# VESC_POWER_SCH.net
KiCad netlist of a schematic drawn in Altium Designer
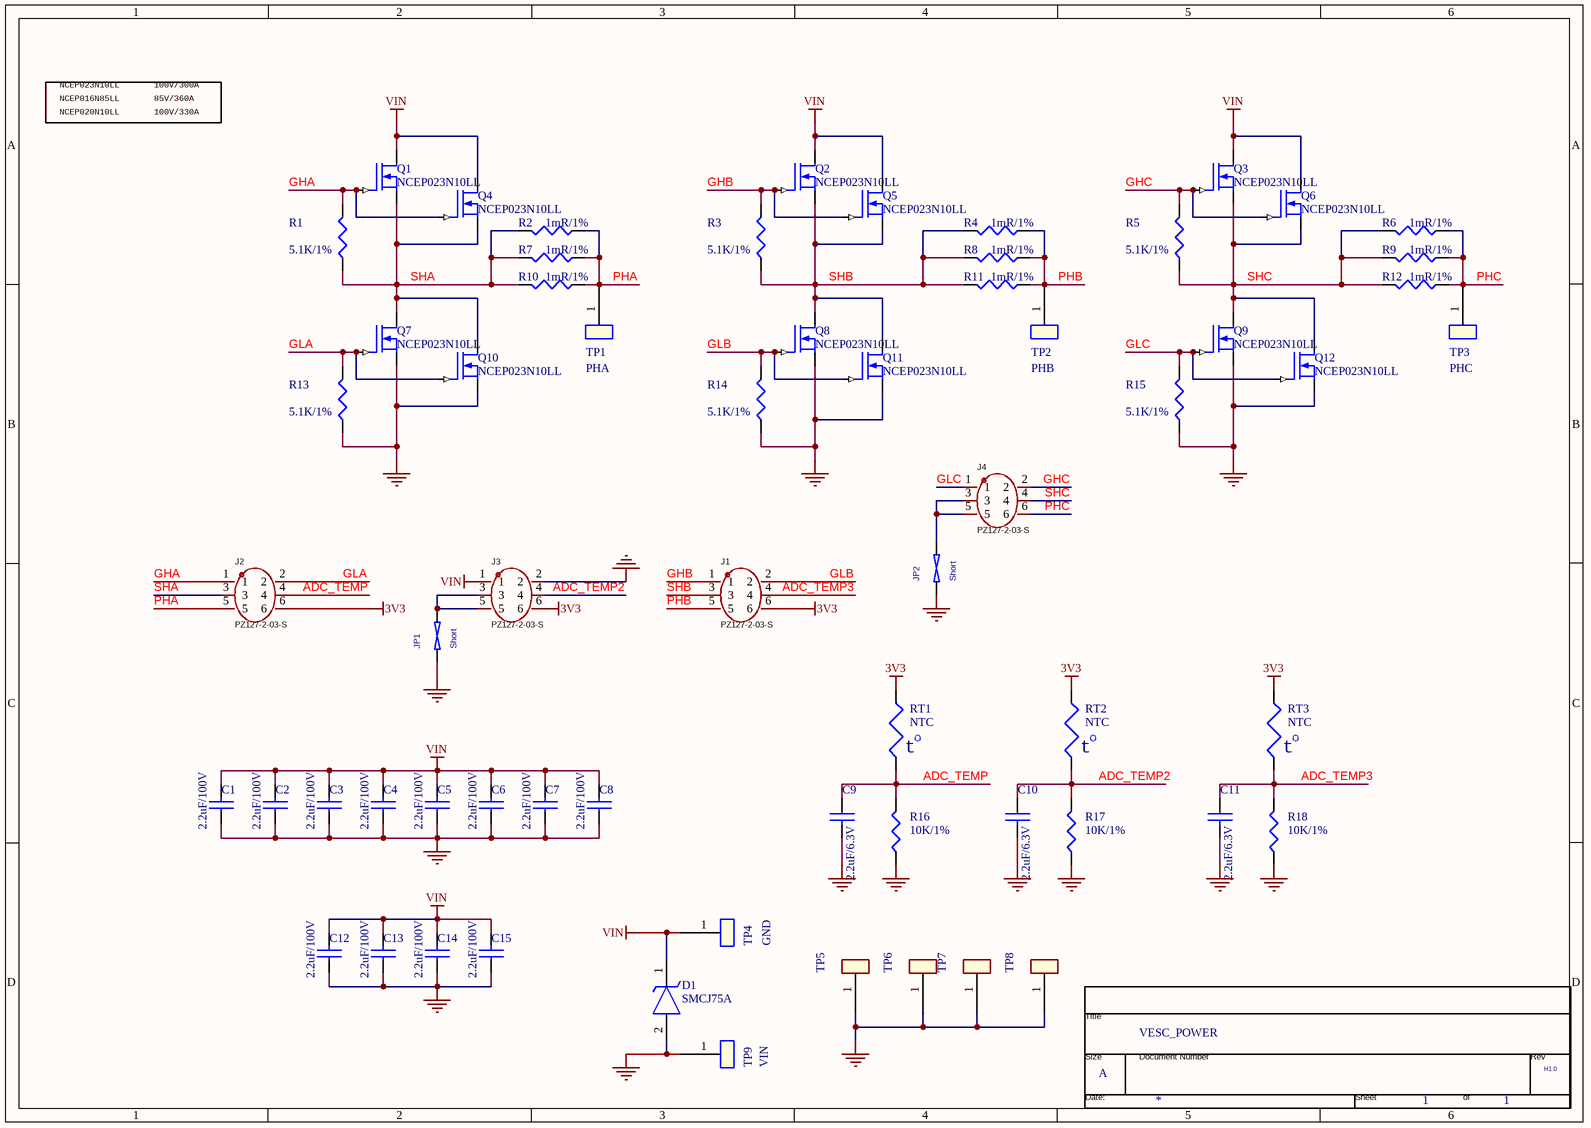
[diagram p0: VESC_POWER_SCH.SchDoc]

(export (version "E")
  (design (tool "Eeschema 10.0.6"))
  (components
    (comp (ref "*")
      (value "TitleBlock0")
      (fields
        (field (name "REVCODE") "H1.0")
        (field (name "TITLE") "VESC_POWER")
        (field (name "PAGE SIZE") "A")
        (field (name "PAGE NUMBER") "1")
        (field (name "PAGE COUNT") "1")
      )
      (libsource (lib "*") (part "TitleBlock0"))
    )
    (comp (ref "C1") (value "2.2uF/100V") (footprint "CAPC3225X230N") (libsource (lib "*") (part "CAP NP")))
    (comp (ref "C2") (value "2.2uF/100V") (footprint "CAPC3225X230N") (libsource (lib "*") (part "CAP NP")))
    (comp (ref "C3") (value "2.2uF/100V") (footprint "CAPC3225X230N") (libsource (lib "*") (part "CAP NP")))
    (comp (ref "C4") (value "2.2uF/100V") (footprint "CAPC3225X230N") (libsource (lib "*") (part "CAP NP")))
    (comp (ref "C5") (value "2.2uF/100V") (footprint "CAPC3225X230N") (libsource (lib "*") (part "CAP NP")))
    (comp (ref "C6") (value "2.2uF/100V") (footprint "CAPC3225X230N") (libsource (lib "*") (part "CAP NP")))
    (comp (ref "C7") (value "2.2uF/100V") (footprint "CAPC3225X230N") (libsource (lib "*") (part "CAP NP")))
    (comp (ref "C8") (value "2.2uF/100V") (footprint "CAPC3225X230N") (libsource (lib "*") (part "CAP NP")))
    (comp (ref "C9") (value "2.2uF/6.3V") (footprint "C0603") (libsource (lib "*") (part "CAP NP")))
    (comp (ref "C10") (value "2.2uF/6.3V") (footprint "C0603") (libsource (lib "*") (part "CAP NP")))
    (comp (ref "C11") (value "2.2uF/6.3V") (footprint "C0603") (libsource (lib "*") (part "CAP NP")))
    (comp (ref "C12") (value "2.2uF/100V") (footprint "CAPC3225X230N") (libsource (lib "*") (part "CAP NP")))
    (comp (ref "C13") (value "2.2uF/100V") (footprint "CAPC3225X230N") (libsource (lib "*") (part "CAP NP")))
    (comp (ref "C14") (value "2.2uF/100V") (footprint "CAPC3225X230N") (libsource (lib "*") (part "CAP NP")))
    (comp (ref "C15") (value "2.2uF/100V") (footprint "CAPC3225X230N") (libsource (lib "*") (part "CAP NP")))
    (comp (ref "D1")
      (value "SMCJ75A")
      (footprint "DIOM7959X262N")
      (description "TVS Diode (Uni-directional)")
      (fields (field (name "MOUSER PART NUMBER") "652-SMCJ75A"))
      (libsource (lib "VESC_POWER_Library") (part "SMCJ75A"))
    )
    (comp (ref "J1")
      (value "PZ127-2-03-S")
      (footprint "HDR-SMD_6P-P1.27-V-M-R2-C3-LS5.3")
      (fields (field (name "MANUFACTURER") "HCTL(华灿天禄)"))
      (libsource (lib "VESC_POWER_Library") (part "PZ127-2-03-S"))
    )
    (comp (ref "J2")
      (value "PZ127-2-03-S")
      (footprint "HDR-SMD_6P-P1.27-V-M-R2-C3-LS5.3")
      (fields (field (name "MANUFACTURER") "HCTL(华灿天禄)"))
      (libsource (lib "VESC_POWER_Library") (part "PZ127-2-03-S"))
    )
    (comp (ref "J3")
      (value "PZ127-2-03-S")
      (footprint "HDR-SMD_6P-P1.27-V-M-R2-C3-LS5.3")
      (fields (field (name "MANUFACTURER") "HCTL(华灿天禄)"))
      (libsource (lib "VESC_POWER_Library") (part "PZ127-2-03-S"))
    )
    (comp (ref "J4")
      (value "PZ127-2-03-S")
      (footprint "HDR-SMD_6P-P1.27-V-M-R2-C3-LS5.3")
      (fields (field (name "MANUFACTURER") "HCTL(华灿天禄)"))
      (libsource (lib "VESC_POWER_Library") (part "PZ127-2-03-S"))
    )
    (comp (ref "JP1")
      (value "Short")
      (footprint "SHORT")
      (description "2 PIN SHORTED TO CONNECT DIFFERENT NETS")
      (fields (field (name "PART_NUMBER") "TMP-442"))
      (libsource (lib "VESC_POWER_Library") (part "SHORT"))
    )
    (comp (ref "JP2")
      (value "Short")
      (footprint "SHORT")
      (description "2 PIN SHORTED TO CONNECT DIFFERENT NETS")
      (fields (field (name "PART_NUMBER") "TMP-442"))
      (libsource (lib "VESC_POWER_Library") (part "SHORT"))
    )
    (comp (ref "Q1") (value "NCEP023N10LL") (footprint "TOLL") (libsource (lib "*") (part "MOSFET N")))
    (comp (ref "Q2") (value "NCEP023N10LL") (footprint "TOLL") (libsource (lib "*") (part "MOSFET N")))
    (comp (ref "Q3") (value "NCEP023N10LL") (footprint "TOLL") (libsource (lib "*") (part "MOSFET N")))
    (comp (ref "Q4") (value "NCEP023N10LL") (footprint "TOLL") (libsource (lib "*") (part "MOSFET N")))
    (comp (ref "Q5") (value "NCEP023N10LL") (footprint "TOLL") (libsource (lib "*") (part "MOSFET N")))
    (comp (ref "Q6") (value "NCEP023N10LL") (footprint "TOLL") (libsource (lib "*") (part "MOSFET N")))
    (comp (ref "Q7") (value "NCEP023N10LL") (footprint "TOLL") (libsource (lib "*") (part "MOSFET N")))
    (comp (ref "Q8") (value "NCEP023N10LL") (footprint "TOLL") (libsource (lib "*") (part "MOSFET N")))
    (comp (ref "Q9") (value "NCEP023N10LL") (footprint "TOLL") (libsource (lib "*") (part "MOSFET N")))
    (comp (ref "Q10") (value "NCEP023N10LL") (footprint "TOLL") (libsource (lib "*") (part "MOSFET N")))
    (comp (ref "Q11") (value "NCEP023N10LL") (footprint "TOLL") (libsource (lib "*") (part "MOSFET N")))
    (comp (ref "Q12") (value "NCEP023N10LL") (footprint "TOLL") (libsource (lib "*") (part "MOSFET N")))
    (comp (ref "R1") (value "5.1K/1%") (footprint "R0603") (libsource (lib "*") (part "RESISTOR")))
    (comp (ref "R2") (value "1mR/1%") (footprint "R2512") (libsource (lib "*") (part "RESISTOR")))
    (comp (ref "R3") (value "5.1K/1%") (footprint "R0603") (libsource (lib "*") (part "RESISTOR")))
    (comp (ref "R4") (value "1mR/1%") (footprint "R2512") (libsource (lib "*") (part "RESISTOR")))
    (comp (ref "R5") (value "5.1K/1%") (footprint "R0603") (libsource (lib "*") (part "RESISTOR")))
    (comp (ref "R6") (value "1mR/1%") (footprint "R2512") (libsource (lib "*") (part "RESISTOR")))
    (comp (ref "R7") (value "1mR/1%") (footprint "R2512") (libsource (lib "*") (part "RESISTOR")))
    (comp (ref "R8") (value "1mR/1%") (footprint "R2512") (libsource (lib "*") (part "RESISTOR")))
    (comp (ref "R9") (value "1mR/1%") (footprint "R2512") (libsource (lib "*") (part "RESISTOR")))
    (comp (ref "R10") (value "1mR/1%") (footprint "R2512") (libsource (lib "*") (part "RESISTOR")))
    (comp (ref "R11") (value "1mR/1%") (footprint "R2512") (libsource (lib "*") (part "RESISTOR")))
    (comp (ref "R12") (value "1mR/1%") (footprint "R2512") (libsource (lib "*") (part "RESISTOR")))
    (comp (ref "R13") (value "5.1K/1%") (footprint "R0603") (libsource (lib "*") (part "RESISTOR")))
    (comp (ref "R14") (value "5.1K/1%") (footprint "R0603") (libsource (lib "*") (part "RESISTOR")))
    (comp (ref "R15") (value "5.1K/1%") (footprint "R0603") (libsource (lib "*") (part "RESISTOR")))
    (comp (ref "R16") (value "10K/1%") (footprint "R0603") (libsource (lib "*") (part "RESISTOR")))
    (comp (ref "R17") (value "10K/1%") (footprint "R0603") (libsource (lib "*") (part "RESISTOR")))
    (comp (ref "R18") (value "10K/1%") (footprint "R0603") (libsource (lib "*") (part "RESISTOR")))
    (comp (ref "RT1") (value "NTC") (footprint "R0603") (libsource (lib "*") (part "NTC")))
    (comp (ref "RT2") (value "NTC") (footprint "R0603") (libsource (lib "*") (part "NTC")))
    (comp (ref "RT3") (value "NTC") (footprint "R0603") (libsource (lib "*") (part "NTC")))
    (comp (ref "TP1") (value "PHA") (footprint "TP_8x8") (libsource (lib "") (part "TEST POINT_1")))
    (comp (ref "TP2") (value "PHB") (footprint "TP_8x8") (libsource (lib "") (part "TEST POINT_1")))
    (comp (ref "TP3") (value "PHC") (footprint "TP_8x8") (libsource (lib "") (part "TEST POINT_1")))
    (comp (ref "TP4") (value "GND") (footprint "TP_8x8") (libsource (lib "*") (part "TEST POINT")))
    (comp (ref "TP5")
      (value "TEST POINT")
      (footprint "HOLE-3.2MM_M")
      (libsource (lib "VESC_POWER_Library") (part "TEST POINT"))
    )
    (comp (ref "TP6")
      (value "TEST POINT")
      (footprint "HOLE-3.2MM_M")
      (libsource (lib "VESC_POWER_Library") (part "TEST POINT"))
    )
    (comp (ref "TP7")
      (value "TEST POINT")
      (footprint "HOLE-3.2MM_M")
      (libsource (lib "VESC_POWER_Library") (part "TEST POINT"))
    )
    (comp (ref "TP8")
      (value "TEST POINT")
      (footprint "HOLE-3.2MM_M")
      (libsource (lib "VESC_POWER_Library") (part "TEST POINT"))
    )
    (comp (ref "TP9") (value "VIN") (footprint "TP_8x8") (libsource (lib "*") (part "TEST POINT")))
  )
  (nets
    (net (code "1") (name "/ADC_TEMP") (class "Default")
      (node (ref "C9") (pin "1") (pinfunction "1_1") (pintype "passive"))
      (node (ref "J2") (pin "4") (pinfunction "4_4") (pintype "passive"))
      (node (ref "R16") (pin "2") (pinfunction "2_2") (pintype "passive"))
      (node (ref "RT1") (pin "2") (pinfunction "2_2") (pintype "passive"))
    )
    (net (code "2") (name "/ADC_TEMP2") (class "Default")
      (node (ref "C10") (pin "1") (pinfunction "1_1") (pintype "passive"))
      (node (ref "J3") (pin "4") (pinfunction "4_4") (pintype "passive"))
      (node (ref "R17") (pin "2") (pinfunction "2_2") (pintype "passive"))
      (node (ref "RT2") (pin "2") (pinfunction "2_2") (pintype "passive"))
    )
    (net (code "3") (name "/ADC_TEMP3") (class "Default")
      (node (ref "C11") (pin "1") (pinfunction "1_1") (pintype "passive"))
      (node (ref "J1") (pin "4") (pinfunction "4_4") (pintype "passive"))
      (node (ref "R18") (pin "2") (pinfunction "2_2") (pintype "passive"))
      (node (ref "RT3") (pin "2") (pinfunction "2_2") (pintype "passive"))
    )
    (net (code "4") (name "/GHA") (class "Default")
      (node (ref "J2") (pin "1") (pinfunction "1_1") (pintype "passive"))
      (node (ref "Q1") (pin "1") (pinfunction "GATE_1") (pintype "input"))
      (node (ref "Q4") (pin "1") (pinfunction "GATE_1") (pintype "input"))
      (node (ref "R1") (pin "2") (pinfunction "2_2") (pintype "passive"))
    )
    (net (code "5") (name "/GHB") (class "Default")
      (node (ref "J1") (pin "1") (pinfunction "1_1") (pintype "passive"))
      (node (ref "Q2") (pin "1") (pinfunction "GATE_1") (pintype "input"))
      (node (ref "Q5") (pin "1") (pinfunction "GATE_1") (pintype "input"))
      (node (ref "R3") (pin "2") (pinfunction "2_2") (pintype "passive"))
    )
    (net (code "6") (name "/GHC") (class "Default")
      (node (ref "J4") (pin "2") (pinfunction "2_2") (pintype "passive"))
      (node (ref "Q3") (pin "1") (pinfunction "GATE_1") (pintype "input"))
      (node (ref "Q6") (pin "1") (pinfunction "GATE_1") (pintype "input"))
      (node (ref "R5") (pin "2") (pinfunction "2_2") (pintype "passive"))
    )
    (net (code "7") (name "/GLA") (class "Default")
      (node (ref "J2") (pin "2") (pinfunction "2_2") (pintype "passive"))
      (node (ref "Q10") (pin "1") (pinfunction "GATE_1") (pintype "input"))
      (node (ref "Q7") (pin "1") (pinfunction "GATE_1") (pintype "input"))
      (node (ref "R13") (pin "2") (pinfunction "2_2") (pintype "passive"))
    )
    (net (code "8") (name "/GLB") (class "Default")
      (node (ref "J1") (pin "2") (pinfunction "2_2") (pintype "passive"))
      (node (ref "Q11") (pin "1") (pinfunction "GATE_1") (pintype "input"))
      (node (ref "Q8") (pin "1") (pinfunction "GATE_1") (pintype "input"))
      (node (ref "R14") (pin "2") (pinfunction "2_2") (pintype "passive"))
    )
    (net (code "9") (name "/GLC") (class "Default")
      (node (ref "J4") (pin "1") (pinfunction "1_1") (pintype "passive"))
      (node (ref "Q12") (pin "1") (pinfunction "GATE_1") (pintype "input"))
      (node (ref "Q9") (pin "1") (pinfunction "GATE_1") (pintype "input"))
      (node (ref "R15") (pin "2") (pinfunction "2_2") (pintype "passive"))
    )
    (net (code "10") (name "/PHA") (class "Default")
      (node (ref "J2") (pin "5") (pinfunction "5_5") (pintype "passive"))
      (node (ref "R10") (pin "1") (pinfunction "1_1") (pintype "passive"))
      (node (ref "R2") (pin "1") (pinfunction "1_1") (pintype "passive"))
      (node (ref "R7") (pin "1") (pinfunction "1_1") (pintype "passive"))
      (node (ref "TP1") (pin "1") (pinfunction "1_1") (pintype "passive"))
    )
    (net (code "11") (name "/PHB") (class "Default")
      (node (ref "J1") (pin "5") (pinfunction "5_5") (pintype "passive"))
      (node (ref "R11") (pin "1") (pinfunction "1_1") (pintype "passive"))
      (node (ref "R4") (pin "1") (pinfunction "1_1") (pintype "passive"))
      (node (ref "R8") (pin "1") (pinfunction "1_1") (pintype "passive"))
      (node (ref "TP2") (pin "1") (pinfunction "1_1") (pintype "passive"))
    )
    (net (code "12") (name "/PHC") (class "Default")
      (node (ref "J4") (pin "6") (pinfunction "6_6") (pintype "passive"))
      (node (ref "R12") (pin "1") (pinfunction "1_1") (pintype "passive"))
      (node (ref "R6") (pin "1") (pinfunction "1_1") (pintype "passive"))
      (node (ref "R9") (pin "1") (pinfunction "1_1") (pintype "passive"))
      (node (ref "TP3") (pin "1") (pinfunction "1_1") (pintype "passive"))
    )
    (net (code "13") (name "/SHA") (class "Default")
      (node (ref "J2") (pin "3") (pinfunction "3_3") (pintype "passive"))
      (node (ref "Q1") (pin "3") (pinfunction "SOURCE_3") (pintype "passive"))
      (node (ref "Q10") (pin "2") (pinfunction "DRAIN_2") (pintype "passive"))
      (node (ref "Q4") (pin "3") (pinfunction "SOURCE_3") (pintype "passive"))
      (node (ref "Q7") (pin "2") (pinfunction "DRAIN_2") (pintype "passive"))
      (node (ref "R1") (pin "1") (pinfunction "1_1") (pintype "passive"))
      (node (ref "R10") (pin "2") (pinfunction "2_2") (pintype "passive"))
      (node (ref "R2") (pin "2") (pinfunction "2_2") (pintype "passive"))
      (node (ref "R7") (pin "2") (pinfunction "2_2") (pintype "passive"))
    )
    (net (code "14") (name "/SHB") (class "Default")
      (node (ref "J1") (pin "3") (pinfunction "3_3") (pintype "passive"))
      (node (ref "Q11") (pin "2") (pinfunction "DRAIN_2") (pintype "passive"))
      (node (ref "Q2") (pin "3") (pinfunction "SOURCE_3") (pintype "passive"))
      (node (ref "Q5") (pin "3") (pinfunction "SOURCE_3") (pintype "passive"))
      (node (ref "Q8") (pin "2") (pinfunction "DRAIN_2") (pintype "passive"))
      (node (ref "R11") (pin "2") (pinfunction "2_2") (pintype "passive"))
      (node (ref "R3") (pin "1") (pinfunction "1_1") (pintype "passive"))
      (node (ref "R4") (pin "2") (pinfunction "2_2") (pintype "passive"))
      (node (ref "R8") (pin "2") (pinfunction "2_2") (pintype "passive"))
    )
    (net (code "15") (name "/SHC") (class "Default")
      (node (ref "J4") (pin "4") (pinfunction "4_4") (pintype "passive"))
      (node (ref "Q12") (pin "2") (pinfunction "DRAIN_2") (pintype "passive"))
      (node (ref "Q3") (pin "3") (pinfunction "SOURCE_3") (pintype "passive"))
      (node (ref "Q6") (pin "3") (pinfunction "SOURCE_3") (pintype "passive"))
      (node (ref "Q9") (pin "2") (pinfunction "DRAIN_2") (pintype "passive"))
      (node (ref "R12") (pin "2") (pinfunction "2_2") (pintype "passive"))
      (node (ref "R5") (pin "1") (pinfunction "1_1") (pintype "passive"))
      (node (ref "R6") (pin "2") (pinfunction "2_2") (pintype "passive"))
      (node (ref "R9") (pin "2") (pinfunction "2_2") (pintype "passive"))
    )
    (net (code "16") (name "3V3") (class "Default")
      (node (ref "J1") (pin "6") (pinfunction "6_6") (pintype "passive"))
      (node (ref "J2") (pin "6") (pinfunction "6_6") (pintype "passive"))
      (node (ref "J3") (pin "6") (pinfunction "6_6") (pintype "passive"))
      (node (ref "RT1") (pin "1") (pinfunction "1_1") (pintype "passive"))
      (node (ref "RT2") (pin "1") (pinfunction "1_1") (pintype "passive"))
      (node (ref "RT3") (pin "1") (pinfunction "1_1") (pintype "passive"))
    )
    (net (code "17") (name "GND") (class "Default")
      (node (ref "C1") (pin "1") (pinfunction "1_1") (pintype "passive"))
      (node (ref "C10") (pin "2") (pinfunction "2_2") (pintype "passive"))
      (node (ref "C11") (pin "2") (pinfunction "2_2") (pintype "passive"))
      (node (ref "C12") (pin "1") (pinfunction "1_1") (pintype "passive"))
      (node (ref "C13") (pin "1") (pinfunction "1_1") (pintype "passive"))
      (node (ref "C14") (pin "1") (pinfunction "1_1") (pintype "passive"))
      (node (ref "C15") (pin "1") (pinfunction "1_1") (pintype "passive"))
      (node (ref "C2") (pin "1") (pinfunction "1_1") (pintype "passive"))
      (node (ref "C3") (pin "1") (pinfunction "1_1") (pintype "passive"))
      (node (ref "C4") (pin "1") (pinfunction "1_1") (pintype "passive"))
      (node (ref "C5") (pin "1") (pinfunction "1_1") (pintype "passive"))
      (node (ref "C6") (pin "1") (pinfunction "1_1") (pintype "passive"))
      (node (ref "C7") (pin "1") (pinfunction "1_1") (pintype "passive"))
      (node (ref "C8") (pin "1") (pinfunction "1_1") (pintype "passive"))
      (node (ref "C9") (pin "2") (pinfunction "2_2") (pintype "passive"))
      (node (ref "D1") (pin "2") (pinfunction "A_2") (pintype "passive"))
      (node (ref "J3") (pin "2") (pinfunction "2_2") (pintype "passive"))
      (node (ref "JP1") (pin "1") (pinfunction "1_1") (pintype "passive"))
      (node (ref "JP2") (pin "1") (pinfunction "1_1") (pintype "passive"))
      (node (ref "Q10") (pin "3") (pinfunction "SOURCE_3") (pintype "passive"))
      (node (ref "Q11") (pin "3") (pinfunction "SOURCE_3") (pintype "passive"))
      (node (ref "Q12") (pin "3") (pinfunction "SOURCE_3") (pintype "passive"))
      (node (ref "Q7") (pin "3") (pinfunction "SOURCE_3") (pintype "passive"))
      (node (ref "Q8") (pin "3") (pinfunction "SOURCE_3") (pintype "passive"))
      (node (ref "Q9") (pin "3") (pinfunction "SOURCE_3") (pintype "passive"))
      (node (ref "R13") (pin "1") (pinfunction "1_1") (pintype "passive"))
      (node (ref "R14") (pin "1") (pinfunction "1_1") (pintype "passive"))
      (node (ref "R15") (pin "1") (pinfunction "1_1") (pintype "passive"))
      (node (ref "R16") (pin "1") (pinfunction "1_1") (pintype "passive"))
      (node (ref "R17") (pin "1") (pinfunction "1_1") (pintype "passive"))
      (node (ref "R18") (pin "1") (pinfunction "1_1") (pintype "passive"))
      (node (ref "TP5") (pin "1") (pinfunction "1_1") (pintype "passive"))
      (node (ref "TP6") (pin "1") (pinfunction "1_1") (pintype "passive"))
      (node (ref "TP7") (pin "1") (pinfunction "1_1") (pintype "passive"))
      (node (ref "TP8") (pin "1") (pinfunction "1_1") (pintype "passive"))
      (node (ref "TP9") (pin "1") (pinfunction "1_1") (pintype "passive"))
    )
    (net (code "18") (name "Net-(J3-Pad3)") (class "Default")
      (node (ref "J3") (pin "3") (pinfunction "3_3") (pintype "passive"))
      (node (ref "J3") (pin "5") (pinfunction "5_5") (pintype "passive"))
      (node (ref "JP1") (pin "2") (pinfunction "2_2") (pintype "passive"))
    )
    (net (code "19") (name "Net-(J4-Pad3)") (class "Default")
      (node (ref "J4") (pin "3") (pinfunction "3_3") (pintype "passive"))
      (node (ref "J4") (pin "5") (pinfunction "5_5") (pintype "passive"))
      (node (ref "JP2") (pin "2") (pinfunction "2_2") (pintype "passive"))
    )
    (net (code "20") (name "VIN") (class "Default")
      (node (ref "C1") (pin "2") (pinfunction "2_2") (pintype "passive"))
      (node (ref "C12") (pin "2") (pinfunction "2_2") (pintype "passive"))
      (node (ref "C13") (pin "2") (pinfunction "2_2") (pintype "passive"))
      (node (ref "C14") (pin "2") (pinfunction "2_2") (pintype "passive"))
      (node (ref "C15") (pin "2") (pinfunction "2_2") (pintype "passive"))
      (node (ref "C2") (pin "2") (pinfunction "2_2") (pintype "passive"))
      (node (ref "C3") (pin "2") (pinfunction "2_2") (pintype "passive"))
      (node (ref "C4") (pin "2") (pinfunction "2_2") (pintype "passive"))
      (node (ref "C5") (pin "2") (pinfunction "2_2") (pintype "passive"))
      (node (ref "C6") (pin "2") (pinfunction "2_2") (pintype "passive"))
      (node (ref "C7") (pin "2") (pinfunction "2_2") (pintype "passive"))
      (node (ref "C8") (pin "2") (pinfunction "2_2") (pintype "passive"))
      (node (ref "D1") (pin "1") (pinfunction "K_1") (pintype "passive"))
      (node (ref "J3") (pin "1") (pinfunction "1_1") (pintype "passive"))
      (node (ref "Q1") (pin "2") (pinfunction "DRAIN_2") (pintype "passive"))
      (node (ref "Q2") (pin "2") (pinfunction "DRAIN_2") (pintype "passive"))
      (node (ref "Q3") (pin "2") (pinfunction "DRAIN_2") (pintype "passive"))
      (node (ref "Q4") (pin "2") (pinfunction "DRAIN_2") (pintype "passive"))
      (node (ref "Q5") (pin "2") (pinfunction "DRAIN_2") (pintype "passive"))
      (node (ref "Q6") (pin "2") (pinfunction "DRAIN_2") (pintype "passive"))
      (node (ref "TP4") (pin "1") (pinfunction "1_1") (pintype "passive"))
    )
  )
)
